# CPU_100M_Ethernet.net
KiCad netlist of a schematic drawn in Altium Designer
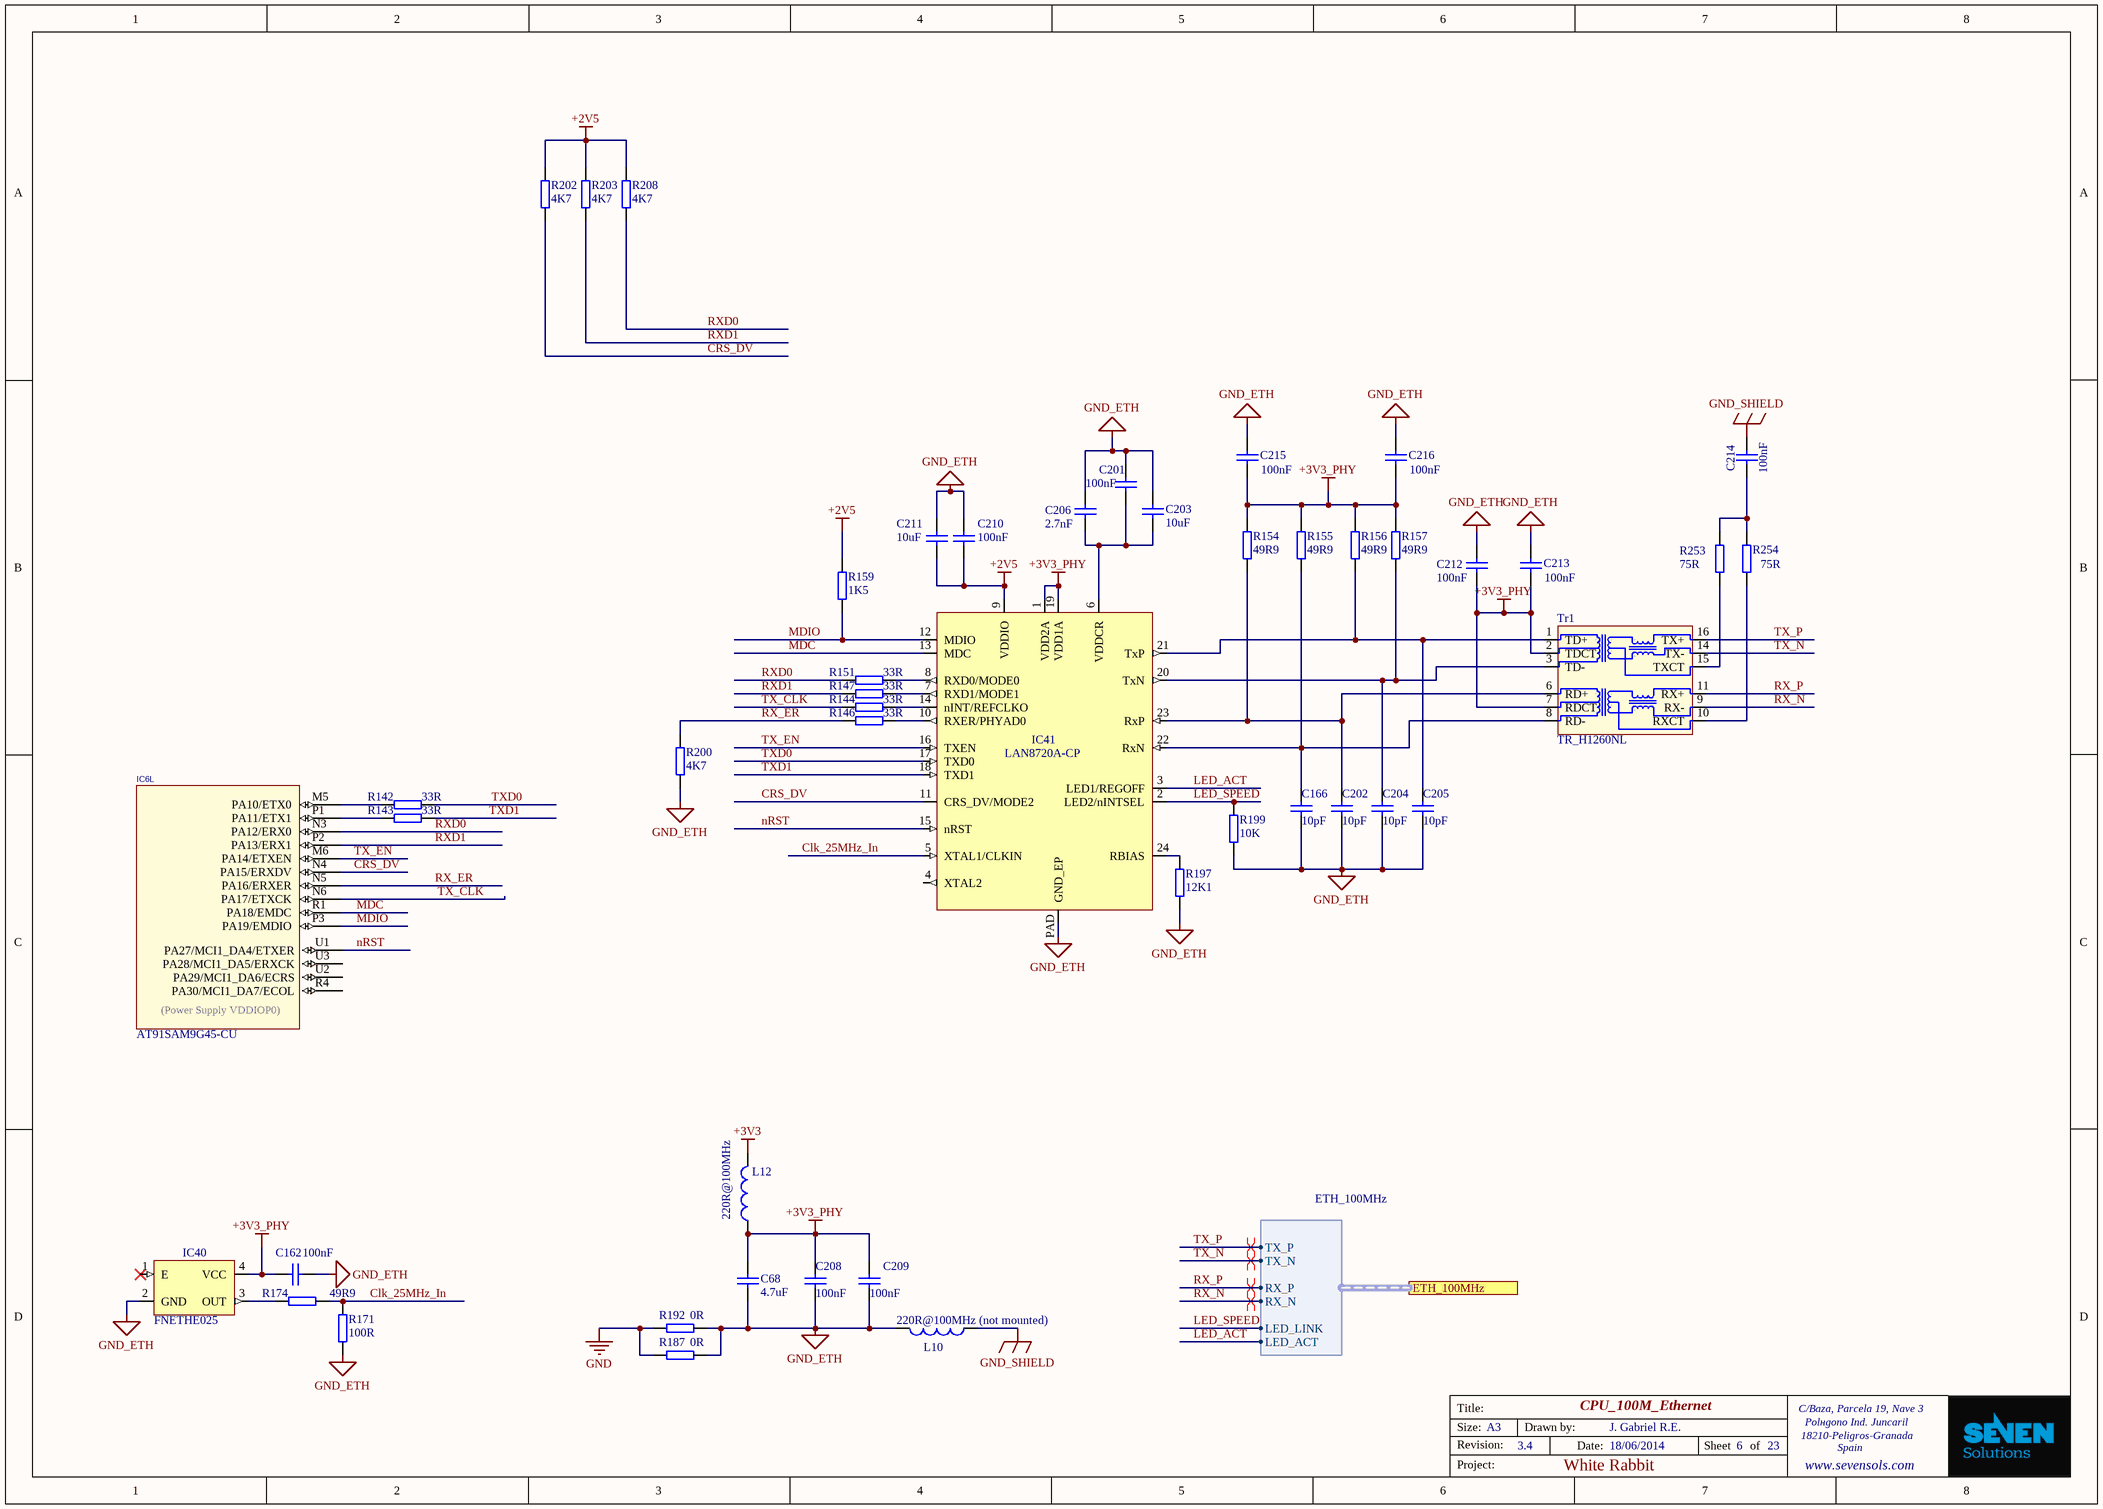
[diagram p0: CPU_100M_Ethernet.SchDoc]

(export (version "E")
  (design (tool "Eeschema 10.0.6"))
  (components
    (comp (ref "C68")
      (value "4.7uF")
      (footprint "CC1608-0603")
      (description "Capacitor")
      (fields
        (field (name "TOLERANCE") "±10%")
        (field (name "VOLTAGE") "10V")
        (field (name "PUBLISHER") "Altium Limited")
      )
      (libsource (lib "wr_switch") (part "Cap"))
    )
    (comp (ref "C162")
      (value "100nF")
      (footprint "CC1005-0402")
      (description "Capacitor")
      (fields
        (field (name "TOLERANCE") "±10%")
        (field (name "VOLTAGE") "16V")
        (field (name "PUBLISHER") "Altium Limited")
      )
      (libsource (lib "wr_switch") (part "Cap"))
    )
    (comp (ref "C166")
      (value "10pF")
      (footprint "CC1005-0402")
      (description "Capacitor")
      (fields
        (field (name "TOLERANCE") "±10%")
        (field (name "VOLTAGE") "50V")
        (field (name "PUBLISHER") "Altium Limited")
      )
      (libsource (lib "wr_switch") (part "Cap"))
    )
    (comp (ref "C201")
      (value "100nF")
      (footprint "CC1005-0402")
      (description "Capacitor")
      (fields
        (field (name "TOLERANCE") "±10%")
        (field (name "VOLTAGE") "16V")
        (field (name "PUBLISHER") "Altium Limited")
      )
      (libsource (lib "wr_switch") (part "Cap"))
    )
    (comp (ref "C202")
      (value "10pF")
      (footprint "CC1005-0402")
      (description "Capacitor")
      (fields
        (field (name "TOLERANCE") "±10%")
        (field (name "VOLTAGE") "50V")
        (field (name "PUBLISHER") "Altium Limited")
      )
      (libsource (lib "wr_switch") (part "Cap"))
    )
    (comp (ref "C203")
      (value "10uF")
      (footprint "CC1608-0603")
      (description "Capacitor")
      (fields
        (field (name "TOLERANCE") "±20%")
        (field (name "VOLTAGE") "6.3V")
        (field (name "PUBLISHER") "Altium Limited")
      )
      (libsource (lib "wr_switch") (part "Cap"))
    )
    (comp (ref "C204")
      (value "10pF")
      (footprint "CC1005-0402")
      (description "Capacitor")
      (fields
        (field (name "TOLERANCE") "±10%")
        (field (name "VOLTAGE") "50V")
        (field (name "PUBLISHER") "Altium Limited")
      )
      (libsource (lib "wr_switch") (part "Cap"))
    )
    (comp (ref "C205")
      (value "10pF")
      (footprint "CC1005-0402")
      (description "Capacitor")
      (fields
        (field (name "TOLERANCE") "±10%")
        (field (name "VOLTAGE") "50V")
        (field (name "PUBLISHER") "Altium Limited")
      )
      (libsource (lib "wr_switch") (part "Cap"))
    )
    (comp (ref "C206")
      (value "2.7nF")
      (footprint "CC1005-0402")
      (description "Capacitor")
      (fields
        (field (name "TOLERANCE") "±10%")
        (field (name "VOLTAGE") "50V")
        (field (name "PUBLISHER") "Altium Limited")
      )
      (libsource (lib "wr_switch") (part "Cap"))
    )
    (comp (ref "C208")
      (value "100nF")
      (footprint "CC1005-0402")
      (description "Capacitor")
      (fields
        (field (name "TOLERANCE") "±10%")
        (field (name "VOLTAGE") "16V")
        (field (name "PUBLISHER") "Altium Limited")
      )
      (libsource (lib "wr_switch") (part "Cap"))
    )
    (comp (ref "C209")
      (value "100nF")
      (footprint "CC1005-0402")
      (description "Capacitor")
      (fields
        (field (name "TOLERANCE") "±10%")
        (field (name "VOLTAGE") "16V")
        (field (name "PUBLISHER") "Altium Limited")
      )
      (libsource (lib "wr_switch") (part "Cap"))
    )
    (comp (ref "C210")
      (value "100nF")
      (footprint "CC1005-0402")
      (description "Capacitor")
      (fields
        (field (name "TOLERANCE") "±10%")
        (field (name "VOLTAGE") "16V")
        (field (name "PUBLISHER") "Altium Limited")
      )
      (libsource (lib "wr_switch") (part "Cap"))
    )
    (comp (ref "C211")
      (value "10uF")
      (footprint "CC1608-0603")
      (description "Capacitor")
      (fields
        (field (name "TOLERANCE") "±20%")
        (field (name "VOLTAGE") "6.3V")
        (field (name "PUBLISHER") "Altium Limited")
      )
      (libsource (lib "wr_switch") (part "Cap"))
    )
    (comp (ref "C212")
      (value "100nF")
      (footprint "CC1005-0402")
      (description "Capacitor")
      (fields
        (field (name "TOLERANCE") "±10%")
        (field (name "VOLTAGE") "16V")
        (field (name "PUBLISHER") "Altium Limited")
      )
      (libsource (lib "wr_switch") (part "Cap"))
    )
    (comp (ref "C213")
      (value "100nF")
      (footprint "CC1005-0402")
      (description "Capacitor")
      (fields
        (field (name "TOLERANCE") "±10%")
        (field (name "VOLTAGE") "16V")
        (field (name "PUBLISHER") "Altium Limited")
      )
      (libsource (lib "wr_switch") (part "Cap"))
    )
    (comp (ref "C214")
      (value "100nF")
      (footprint "CAPR500-250X720X650")
      (description "Non-polarised capacitor")
      (fields
        (field (name "PART NUMBER") "CPER_100NF_100V_10%_500-250X720X650")
        (field (name "VOLTAGE") "100VDC/63VAC")
        (field (name "AUTHOR") "CERN DEM JLC")
      )
      (libsource (lib "Capacitors") (part "Capacitor - non polarized"))
    )
    (comp (ref "C215")
      (value "100nF")
      (footprint "CC1005-0402")
      (description "Capacitor")
      (fields
        (field (name "TOLERANCE") "±10%")
        (field (name "VOLTAGE") "16V")
        (field (name "PUBLISHER") "Altium Limited")
      )
      (libsource (lib "wr_switch") (part "Cap"))
    )
    (comp (ref "C216")
      (value "100nF")
      (footprint "CC1005-0402")
      (description "Capacitor")
      (fields
        (field (name "TOLERANCE") "±10%")
        (field (name "VOLTAGE") "16V")
        (field (name "PUBLISHER") "Altium Limited")
      )
      (libsource (lib "wr_switch") (part "Cap"))
    )
    (comp (ref "IC6")
      (value "AT91SAM9G45-CU")
      (footprint "TFBGA324")
      (description "Atmel 400MHz ARM926 MCU")
      (libsource (lib "wr_switch") (part "AT91SAM9G45-CU"))
    )
    (comp (ref "IC40")
      (value "FNETHE025")
      (footprint "SPXO")
      (description "SMD oscillator 3.3V (Elfa)")
      (libsource (lib "wr_switch") (part "OSC_CFPS-73"))
    )
    (comp (ref "IC41")
      (value "LAN8720A-CP")
      (footprint "QFN50P400X400-24W4M")
      (description "RMII ethernet transceiver with auto MIDIX")
      (fields (field (name "MANUFACTURER") "SMSC"))
      (libsource (lib "wr_switch") (part "LAN8720A-CP"))
    )
    (comp (ref "L10")
      (value "220R@100MHz Ferrite Bead")
      (footprint "0603")
      (description "ferrite bead")
      (fields (field (name "IMPEDANCE") "220R@100MHz (not mounted)"))
      (libsource (lib "wr_switch") (part "L_FERRITE_BEAD"))
    )
    (comp (ref "L12")
      (value "220R@100MHz Ferrite Bead")
      (footprint "0603")
      (description "ferrite bead")
      (fields (field (name "IMPEDANCE") "220R@100MHz"))
      (libsource (lib "wr_switch") (part "L_FERRITE_BEAD"))
    )
    (comp (ref "R142")
      (value "33R")
      (footprint "0402")
      (description "SMD Resistor")
      (fields (field (name "TOLERANCE") "±1%"))
      (libsource (lib "wr_switch") (part "RES_SMD"))
    )
    (comp (ref "R143")
      (value "33R")
      (footprint "0402")
      (description "SMD Resistor")
      (fields (field (name "TOLERANCE") "±1%"))
      (libsource (lib "wr_switch") (part "RES_SMD"))
    )
    (comp (ref "R144")
      (value "33R")
      (footprint "0402")
      (description "SMD Resistor")
      (fields (field (name "TOLERANCE") "±1%"))
      (libsource (lib "wr_switch") (part "RES_SMD"))
    )
    (comp (ref "R146")
      (value "33R")
      (footprint "0402")
      (description "SMD Resistor")
      (fields (field (name "TOLERANCE") "±1%"))
      (libsource (lib "wr_switch") (part "RES_SMD"))
    )
    (comp (ref "R147")
      (value "33R")
      (footprint "0402")
      (description "SMD Resistor")
      (fields (field (name "TOLERANCE") "±1%"))
      (libsource (lib "wr_switch") (part "RES_SMD"))
    )
    (comp (ref "R151")
      (value "33R")
      (footprint "0402")
      (description "SMD Resistor")
      (fields (field (name "TOLERANCE") "±1%"))
      (libsource (lib "wr_switch") (part "RES_SMD"))
    )
    (comp (ref "R154")
      (value "49R9")
      (footprint "0603")
      (description "SMD Resistor")
      (fields (field (name "TOLERANCE") "±1%"))
      (libsource (lib "wr_switch") (part "RES_SMD"))
    )
    (comp (ref "R155")
      (value "49R9")
      (footprint "0603")
      (description "SMD Resistor")
      (fields (field (name "TOLERANCE") "±1%"))
      (libsource (lib "wr_switch") (part "RES_SMD"))
    )
    (comp (ref "R156")
      (value "49R9")
      (footprint "0603")
      (description "SMD Resistor")
      (fields (field (name "TOLERANCE") "±1%"))
      (libsource (lib "wr_switch") (part "RES_SMD"))
    )
    (comp (ref "R157")
      (value "49R9")
      (footprint "0603")
      (description "SMD Resistor")
      (fields (field (name "TOLERANCE") "±1%"))
      (libsource (lib "wr_switch") (part "RES_SMD"))
    )
    (comp (ref "R159")
      (value "1K5")
      (footprint "0402")
      (description "SMD Resistor")
      (fields (field (name "TOLERANCE") "±1%"))
      (libsource (lib "wr_switch") (part "RES_SMD"))
    )
    (comp (ref "R171")
      (value "100R")
      (footprint "0402")
      (description "SMD Resistor")
      (fields (field (name "TOLERANCE") "±1%"))
      (libsource (lib "wr_switch") (part "RES_SMD"))
    )
    (comp (ref "R174")
      (value "49R9")
      (footprint "0402")
      (description "SMD Resistor")
      (fields (field (name "TOLERANCE") "±1%"))
      (libsource (lib "wr_switch") (part "RES_SMD"))
    )
    (comp (ref "R187")
      (value "0R")
      (footprint "0402")
      (description "SMD Resistor")
      (fields (field (name "TOLERANCE") "Jumper"))
      (libsource (lib "wr_switch") (part "RES_SMD"))
    )
    (comp (ref "R192")
      (value "0R")
      (footprint "0402")
      (description "SMD Resistor")
      (fields (field (name "TOLERANCE") "Jumper"))
      (libsource (lib "wr_switch") (part "RES_SMD"))
    )
    (comp (ref "R197")
      (value "12K1")
      (footprint "0402")
      (description "SMD Resistor")
      (fields (field (name "TOLERANCE") "±1%"))
      (libsource (lib "wr_switch") (part "RES_SMD"))
    )
    (comp (ref "R199")
      (value "10K")
      (footprint "0402")
      (description "SMD Resistor")
      (fields (field (name "TOLERANCE") "±1%") (field (name "Comment") "10k"))
      (libsource (lib "wr_switch") (part "RES_SMD"))
    )
    (comp (ref "R200")
      (value "4K7")
      (footprint "0402")
      (description "SMD Resistor")
      (fields (field (name "TOLERANCE") "±1%"))
      (libsource (lib "wr_switch") (part "RES_SMD"))
    )
    (comp (ref "R202")
      (value "4K7")
      (footprint "0402")
      (description "SMD Resistor")
      (fields (field (name "TOLERANCE") "±1%"))
      (libsource (lib "wr_switch") (part "RES_SMD"))
    )
    (comp (ref "R203")
      (value "4K7")
      (footprint "0402")
      (description "SMD Resistor")
      (fields (field (name "TOLERANCE") "±1%"))
      (libsource (lib "wr_switch") (part "RES_SMD"))
    )
    (comp (ref "R208")
      (value "4K7")
      (footprint "0402")
      (description "SMD Resistor")
      (fields (field (name "TOLERANCE") "±1%"))
      (libsource (lib "wr_switch") (part "RES_SMD"))
    )
    (comp (ref "R253")
      (value "75R")
      (footprint "0402")
      (description "SMD Resistor")
      (fields (field (name "TOLERANCE") "±1%"))
      (libsource (lib "wr_switch") (part "RES_SMD"))
    )
    (comp (ref "R254")
      (value "75R")
      (footprint "0402")
      (description "SMD Resistor")
      (fields (field (name "TOLERANCE") "±1%"))
      (libsource (lib "wr_switch") (part "RES_SMD"))
    )
    (comp (ref "Tr1")
      (value "TR_H1260NL")
      (footprint "7S_WR:H1260NL")
      (description "ethernet trafo (TME)")
      (libsource (lib "wr_switch") (part "TR_H1260NL"))
    )
  )
  (nets
    (net (code "2") (name "+2V5") (class "Default")
      (node (ref "C210") (pin "2") (pinfunction "2_2") (pintype "passive"))
      (node (ref "C211") (pin "2") (pinfunction "2_2") (pintype "passive"))
      (node (ref "IC41") (pin "9") (pinfunction "VDDIO_9") (pintype "power_in"))
      (node (ref "R159") (pin "2") (pinfunction "2_2") (pintype "passive"))
      (node (ref "R202") (pin "2") (pinfunction "2_2") (pintype "passive"))
      (node (ref "R203") (pin "2") (pinfunction "2_2") (pintype "passive"))
      (node (ref "R208") (pin "2") (pinfunction "2_2") (pintype "passive"))
    )
    (net (code "3") (name "+3V3") (class "Default")
      (node (ref "L12") (pin "2") (pinfunction "2_2") (pintype "passive"))
    )
    (net (code "4") (name "+3V3_PHY") (class "Default")
      (node (ref "C162") (pin "2") (pinfunction "2_2") (pintype "passive"))
      (node (ref "C208") (pin "1") (pinfunction "1_1") (pintype "passive"))
      (node (ref "C209") (pin "1") (pinfunction "1_1") (pintype "passive"))
      (node (ref "C212") (pin "1") (pinfunction "1_1") (pintype "passive"))
      (node (ref "C213") (pin "1") (pinfunction "1_1") (pintype "passive"))
      (node (ref "C215") (pin "1") (pinfunction "1_1") (pintype "passive"))
      (node (ref "C216") (pin "1") (pinfunction "1_1") (pintype "passive"))
      (node (ref "C68") (pin "2") (pinfunction "2_2") (pintype "passive"))
      (node (ref "IC40") (pin "4") (pinfunction "VCC_4") (pintype "power_in"))
      (node (ref "IC41") (pin "1") (pinfunction "VDD2A_1") (pintype "power_in"))
      (node (ref "IC41") (pin "19") (pinfunction "VDD1A_19") (pintype "power_in"))
      (node (ref "L12") (pin "1") (pinfunction "1_1") (pintype "passive"))
      (node (ref "R154") (pin "2") (pinfunction "2_2") (pintype "passive"))
      (node (ref "R155") (pin "2") (pinfunction "2_2") (pintype "passive"))
      (node (ref "R156") (pin "2") (pinfunction "2_2") (pintype "passive"))
      (node (ref "R157") (pin "2") (pinfunction "2_2") (pintype "passive"))
      (node (ref "Tr1") (pin "2") (pinfunction "TDCT_2") (pintype "passive"))
      (node (ref "Tr1") (pin "7") (pinfunction "RDCT_7") (pintype "passive"))
    )
    (net (code "5") (name "/CRS_DV") (class "Default")
      (node (ref "IC41") (pin "11") (pinfunction "CRS_DV/MODE2_11") (pintype "bidirectional"))
      (node (ref "IC6") (pin "N4") (pinfunction "PA15/ERXDV_N4") (pintype "bidirectional"))
      (node (ref "R202") (pin "1") (pinfunction "1_1") (pintype "passive"))
    )
    (net (code "6") (name "/Clk_25MHz_In") (class "Default")
      (node (ref "IC41") (pin "5") (pinfunction "XTAL1/CLKIN_5") (pintype "input"))
      (node (ref "R171") (pin "2") (pinfunction "2_2") (pintype "passive"))
      (node (ref "R174") (pin "1") (pinfunction "1_1") (pintype "passive"))
    )
    (net (code "7") (name "/LED_ACT") (class "Default")
      (node (ref "IC41") (pin "3") (pinfunction "LED1/REGOFF_3") (pintype "bidirectional"))
    )
    (net (code "8") (name "/LED_SPEED") (class "Default")
      (node (ref "IC41") (pin "2") (pinfunction "LED2/nINTSEL_2") (pintype "bidirectional"))
      (node (ref "R199") (pin "2") (pinfunction "2_2") (pintype "passive"))
    )
    (net (code "9") (name "/MDC") (class "Default")
      (node (ref "IC41") (pin "13") (pinfunction "MDC_13") (pintype "bidirectional"))
      (node (ref "IC6") (pin "R1") (pinfunction "PA18/EMDC_R1") (pintype "bidirectional"))
    )
    (net (code "10") (name "/MDIO") (class "Default")
      (node (ref "IC41") (pin "12") (pinfunction "MDIO_12") (pintype "bidirectional"))
      (node (ref "IC6") (pin "P3") (pinfunction "PA19/EMDIO_P3") (pintype "bidirectional"))
      (node (ref "R159") (pin "1") (pinfunction "1_1") (pintype "passive"))
    )
    (net (code "11") (name "/RXD0") (class "Default")
      (node (ref "IC6") (pin "N3") (pinfunction "PA12/ERX0_N3") (pintype "bidirectional"))
      (node (ref "R151") (pin "1") (pinfunction "1_1") (pintype "passive"))
      (node (ref "R208") (pin "1") (pinfunction "1_1") (pintype "passive"))
    )
    (net (code "12") (name "/RXD1") (class "Default")
      (node (ref "IC6") (pin "P2") (pinfunction "PA13/ERX1_P2") (pintype "bidirectional"))
      (node (ref "R147") (pin "1") (pinfunction "1_1") (pintype "passive"))
      (node (ref "R203") (pin "1") (pinfunction "1_1") (pintype "passive"))
    )
    (net (code "13") (name "/RX_ER") (class "Default")
      (node (ref "IC6") (pin "N5") (pinfunction "PA16/ERXER_N5") (pintype "bidirectional"))
      (node (ref "R146") (pin "1") (pinfunction "1_1") (pintype "passive"))
      (node (ref "R200") (pin "1") (pinfunction "1_1") (pintype "passive"))
    )
    (net (code "14") (name "/RX_N") (class "Default")
      (node (ref "Tr1") (pin "9") (pinfunction "RX-_9") (pintype "passive"))
    )
    (net (code "15") (name "/RX_P") (class "Default")
      (node (ref "Tr1") (pin "11") (pinfunction "RX+_11") (pintype "passive"))
    )
    (net (code "16") (name "/TXD0") (class "Default")
      (node (ref "IC41") (pin "17") (pinfunction "TXD0_17") (pintype "input"))
      (node (ref "R142") (pin "2") (pinfunction "2_2") (pintype "passive"))
    )
    (net (code "17") (name "/TXD1") (class "Default")
      (node (ref "IC41") (pin "18") (pinfunction "TXD1_18") (pintype "input"))
      (node (ref "R143") (pin "2") (pinfunction "2_2") (pintype "passive"))
    )
    (net (code "18") (name "/TX_CLK") (class "Default")
      (node (ref "IC6") (pin "N6") (pinfunction "PA17/ETXCK_N6") (pintype "bidirectional"))
      (node (ref "R144") (pin "1") (pinfunction "1_1") (pintype "passive"))
    )
    (net (code "19") (name "/TX_EN") (class "Default")
      (node (ref "IC41") (pin "16") (pinfunction "TXEN_16") (pintype "input"))
      (node (ref "IC6") (pin "M6") (pinfunction "PA14/ETXEN_M6") (pintype "bidirectional"))
    )
    (net (code "20") (name "/TX_N") (class "Default")
      (node (ref "Tr1") (pin "14") (pinfunction "TX-_14") (pintype "passive"))
    )
    (net (code "21") (name "/TX_P") (class "Default")
      (node (ref "Tr1") (pin "16") (pinfunction "TX+_16") (pintype "passive"))
    )
    (net (code "22") (name "/nRST") (class "Default")
      (node (ref "IC41") (pin "15") (pinfunction "nRST_15") (pintype "input"))
      (node (ref "IC6") (pin "U1") (pinfunction "PA27/MCI1_DA4/ETXER_U1") (pintype "bidirectional"))
    )
    (net (code "24") (name "GND") (class "Default")
      (node (ref "R187") (pin "2") (pinfunction "2_2") (pintype "passive"))
      (node (ref "R192") (pin "2") (pinfunction "2_2") (pintype "passive"))
    )
    (net (code "25") (name "GND_ETH") (class "Default")
      (node (ref "C162") (pin "1") (pinfunction "1_1") (pintype "passive"))
      (node (ref "C166") (pin "1") (pinfunction "1_1") (pintype "passive"))
      (node (ref "C201") (pin "1") (pinfunction "1_1") (pintype "passive"))
      (node (ref "C202") (pin "1") (pinfunction "1_1") (pintype "passive"))
      (node (ref "C203") (pin "1") (pinfunction "1_1") (pintype "passive"))
      (node (ref "C204") (pin "1") (pinfunction "1_1") (pintype "passive"))
      (node (ref "C205") (pin "1") (pinfunction "1_1") (pintype "passive"))
      (node (ref "C206") (pin "1") (pinfunction "1_1") (pintype "passive"))
      (node (ref "C208") (pin "2") (pinfunction "2_2") (pintype "passive"))
      (node (ref "C209") (pin "2") (pinfunction "2_2") (pintype "passive"))
      (node (ref "C210") (pin "1") (pinfunction "1_1") (pintype "passive"))
      (node (ref "C211") (pin "1") (pinfunction "1_1") (pintype "passive"))
      (node (ref "C212") (pin "2") (pinfunction "2_2") (pintype "passive"))
      (node (ref "C213") (pin "2") (pinfunction "2_2") (pintype "passive"))
      (node (ref "C215") (pin "2") (pinfunction "2_2") (pintype "passive"))
      (node (ref "C216") (pin "2") (pinfunction "2_2") (pintype "passive"))
      (node (ref "C68") (pin "1") (pinfunction "1_1") (pintype "passive"))
      (node (ref "IC40") (pin "2") (pinfunction "GND_2") (pintype "power_in"))
      (node (ref "IC41") (pin "PAD") (pinfunction "GND_EP_PAD") (pintype "power_in"))
      (node (ref "L10") (pin "2") (pinfunction "2_2") (pintype "passive"))
      (node (ref "R171") (pin "1") (pinfunction "1_1") (pintype "passive"))
      (node (ref "R187") (pin "1") (pinfunction "1_1") (pintype "passive"))
      (node (ref "R192") (pin "1") (pinfunction "1_1") (pintype "passive"))
      (node (ref "R197") (pin "2") (pinfunction "2_2") (pintype "passive"))
      (node (ref "R199") (pin "1") (pinfunction "1_1") (pintype "passive"))
      (node (ref "R200") (pin "2") (pinfunction "2_2") (pintype "passive"))
    )
    (net (code "26") (name "GND_SHIELD") (class "Default")
      (node (ref "C214") (pin "2") (pinfunction "2_2") (pintype "passive"))
      (node (ref "L10") (pin "1") (pinfunction "1_1") (pintype "passive"))
    )
    (net (code "27") (name "Net-(C214-Pad1)") (class "Default")
      (node (ref "C214") (pin "1") (pinfunction "1_1") (pintype "passive"))
      (node (ref "R253") (pin "2") (pinfunction "2_2") (pintype "passive"))
      (node (ref "R254") (pin "2") (pinfunction "2_2") (pintype "passive"))
    )
    (net (code "28") (name "Net-(IC6L-PA10{slash}ETX0)") (class "Default")
      (node (ref "IC6") (pin "M5") (pinfunction "PA10/ETX0_M5") (pintype "bidirectional"))
      (node (ref "R142") (pin "1") (pinfunction "1_1") (pintype "passive"))
    )
    (net (code "29") (name "Net-(IC6L-PA11{slash}ETX1)") (class "Default")
      (node (ref "IC6") (pin "P1") (pinfunction "PA11/ETX1_P1") (pintype "bidirectional"))
      (node (ref "R143") (pin "1") (pinfunction "1_1") (pintype "passive"))
    )
    (net (code "30") (name "Net-(IC40-OUT)") (class "Default")
      (node (ref "IC40") (pin "3") (pinfunction "OUT_3") (pintype "output"))
      (node (ref "R174") (pin "2") (pinfunction "2_2") (pintype "passive"))
    )
    (net (code "31") (name "Net-(IC41-RBIAS)") (class "Default")
      (node (ref "IC41") (pin "24") (pinfunction "RBIAS_24") (pintype "passive"))
      (node (ref "R197") (pin "1") (pinfunction "1_1") (pintype "passive"))
    )
    (net (code "32") (name "Net-(IC41-RXD0{slash}MODE0)") (class "Default")
      (node (ref "IC41") (pin "8") (pinfunction "RXD0/MODE0_8") (pintype "output"))
      (node (ref "R151") (pin "2") (pinfunction "2_2") (pintype "passive"))
    )
    (net (code "33") (name "Net-(IC41-RXD1{slash}MODE1)") (class "Default")
      (node (ref "IC41") (pin "7") (pinfunction "RXD1/MODE1_7") (pintype "output"))
      (node (ref "R147") (pin "2") (pinfunction "2_2") (pintype "passive"))
    )
    (net (code "34") (name "Net-(IC41-RXER{slash}PHYAD0)") (class "Default")
      (node (ref "IC41") (pin "10") (pinfunction "RXER/PHYAD0_10") (pintype "output"))
      (node (ref "R146") (pin "2") (pinfunction "2_2") (pintype "passive"))
    )
    (net (code "35") (name "Net-(IC41-RxN)") (class "Default")
      (node (ref "C166") (pin "2") (pinfunction "2_2") (pintype "passive"))
      (node (ref "IC41") (pin "22") (pinfunction "RxN_22") (pintype "input"))
      (node (ref "R155") (pin "1") (pinfunction "1_1") (pintype "passive"))
      (node (ref "Tr1") (pin "8") (pinfunction "RD-_8") (pintype "passive"))
    )
    (net (code "36") (name "Net-(IC41-RxP)") (class "Default")
      (node (ref "C202") (pin "2") (pinfunction "2_2") (pintype "passive"))
      (node (ref "IC41") (pin "23") (pinfunction "RxP_23") (pintype "input"))
      (node (ref "R154") (pin "1") (pinfunction "1_1") (pintype "passive"))
      (node (ref "Tr1") (pin "6") (pinfunction "RD+_6") (pintype "passive"))
    )
    (net (code "37") (name "Net-(IC41-TxN)") (class "Default")
      (node (ref "C204") (pin "2") (pinfunction "2_2") (pintype "passive"))
      (node (ref "IC41") (pin "20") (pinfunction "TxN_20") (pintype "output"))
      (node (ref "R157") (pin "1") (pinfunction "1_1") (pintype "passive"))
      (node (ref "Tr1") (pin "3") (pinfunction "TD-_3") (pintype "passive"))
    )
    (net (code "38") (name "Net-(IC41-TxP)") (class "Default")
      (node (ref "C205") (pin "2") (pinfunction "2_2") (pintype "passive"))
      (node (ref "IC41") (pin "21") (pinfunction "TxP_21") (pintype "output"))
      (node (ref "R156") (pin "1") (pinfunction "1_1") (pintype "passive"))
      (node (ref "Tr1") (pin "1") (pinfunction "TD+_1") (pintype "passive"))
    )
    (net (code "39") (name "Net-(IC41-VDDCR)") (class "Default")
      (node (ref "C201") (pin "2") (pinfunction "2_2") (pintype "passive"))
      (node (ref "C203") (pin "2") (pinfunction "2_2") (pintype "passive"))
      (node (ref "C206") (pin "2") (pinfunction "2_2") (pintype "passive"))
      (node (ref "IC41") (pin "6") (pinfunction "VDDCR_6") (pintype "power_in"))
    )
    (net (code "40") (name "Net-(IC41-nINT{slash}REFCLKO)") (class "Default")
      (node (ref "IC41") (pin "14") (pinfunction "nINT/REFCLKO_14") (pintype "bidirectional"))
      (node (ref "R144") (pin "2") (pinfunction "2_2") (pintype "passive"))
    )
    (net (code "41") (name "Net-(Tr1-RXCT)") (class "Default")
      (node (ref "R254") (pin "1") (pinfunction "1_1") (pintype "passive"))
      (node (ref "Tr1") (pin "10") (pinfunction "RXCT_10") (pintype "passive"))
    )
    (net (code "42") (name "Net-(Tr1-TXCT)") (class "Default")
      (node (ref "R253") (pin "1") (pinfunction "1_1") (pintype "passive"))
      (node (ref "Tr1") (pin "15") (pinfunction "TXCT_15") (pintype "passive"))
    )
    (net (code "43") (name "unconnected-(IC6L-PA28{slash}MCI1_DA5{slash}ERXCK-PadU3)") (class "Default")
      (node (ref "IC6") (pin "U3") (pinfunction "PA28/MCI1_DA5/ERXCK_U3") (pintype "bidirectional"))
    )
    (net (code "44") (name "unconnected-(IC6L-PA29{slash}MCI1_DA6{slash}ECRS-PadU2)") (class "Default")
      (node (ref "IC6") (pin "U2") (pinfunction "PA29/MCI1_DA6/ECRS_U2") (pintype "bidirectional"))
    )
    (net (code "45") (name "unconnected-(IC6L-PA30{slash}MCI1_DA7{slash}ECOL-PadR4)") (class "Default")
      (node (ref "IC6") (pin "R4") (pinfunction "PA30/MCI1_DA7/ECOL_R4") (pintype "bidirectional"))
    )
    (net (code "46") (name "unconnected-(IC40-E-Pad1)") (class "Default")
      (node (ref "IC40") (pin "1") (pinfunction "E_1") (pintype "input+no_connect"))
    )
    (net (code "47") (name "unconnected-(IC41-XTAL2-Pad4)") (class "Default")
      (node (ref "IC41") (pin "4") (pinfunction "XTAL2_4") (pintype "output"))
    )
  )
)
